# 14DoF_MPU9150_ADXL375.net
KiCad netlist of a schematic drawn in EAGLE
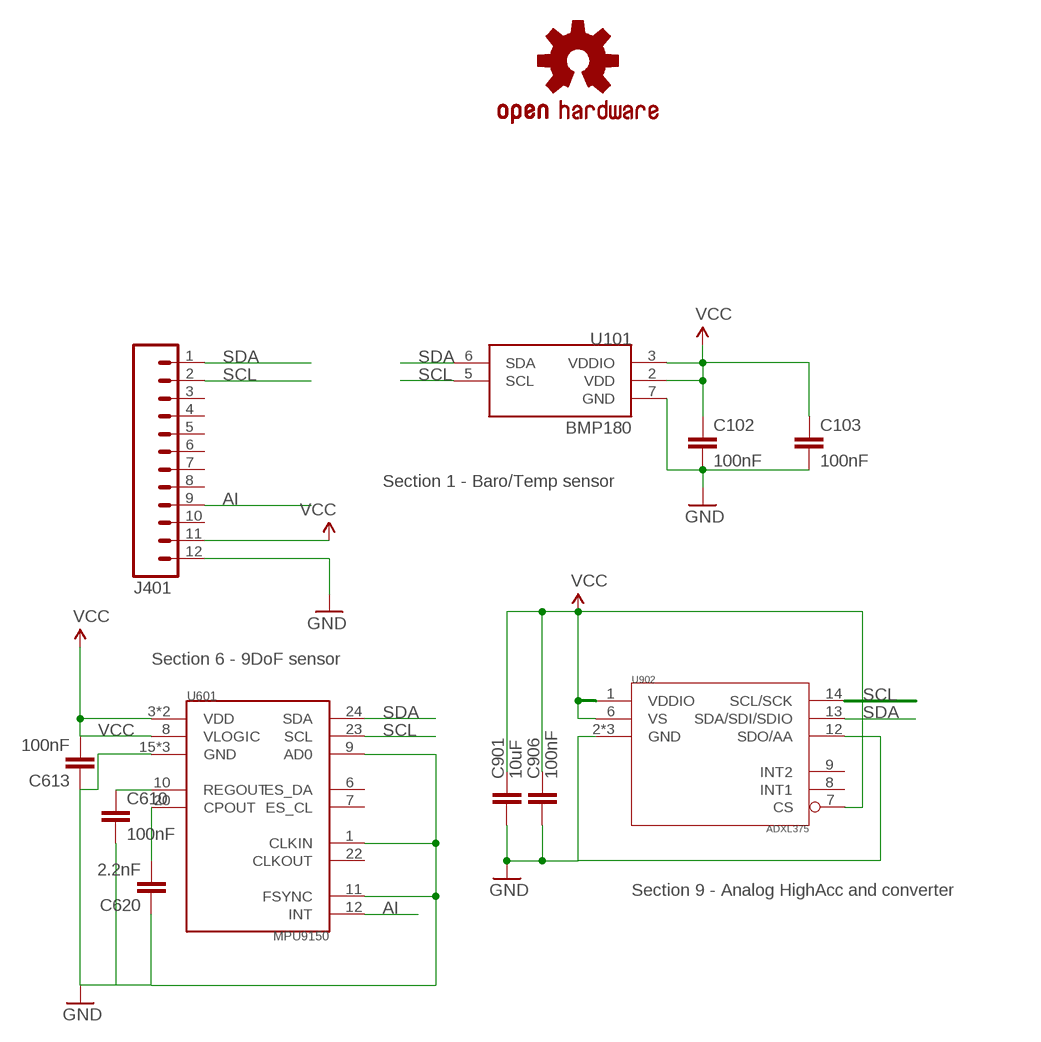
[diagram p0: schematic, sheet 1]

(export (version "E")
  (design (tool "Eeschema 10.0.6"))
  (components
    (comp (ref "C102")
      (value "100nF")
      (footprint "eagle-import:0603-CAP")
      (libsource (lib "eagle-import") (part "CAP0603-CAP"))
    )
    (comp (ref "C103")
      (value "100nF")
      (footprint "eagle-import:0603-CAP")
      (libsource (lib "eagle-import") (part "CAP0603-CAP"))
    )
    (comp (ref "C610")
      (value "100nF")
      (footprint "eagle-import:0603-CAP")
      (libsource (lib "eagle-import") (part "CAP0603-CAP"))
    )
    (comp (ref "C613")
      (value "100nF")
      (footprint "eagle-import:0603-CAP")
      (libsource (lib "eagle-import") (part "CAP0603-CAP"))
    )
    (comp (ref "C620")
      (value "2.2nF")
      (footprint "eagle-import:0603-CAP")
      (libsource (lib "eagle-import") (part "CAP0603-CAP"))
    )
    (comp (ref "C901")
      (value "10uF")
      (footprint "eagle-import:0603-CAP")
      (libsource (lib "eagle-import") (part "CAP0603-CAP"))
    )
    (comp (ref "C906")
      (value "100nF")
      (footprint "eagle-import:0603-CAP")
      (libsource (lib "eagle-import") (part "CAP0603-CAP"))
    )
    (comp (ref "J401")
      (value "M12PTH")
      (footprint "eagle-import:1X12")
      (libsource (lib "eagle-import") (part "M12PTH"))
    )
    (comp (ref "U$2")
      (value "OSHW-LOGOS")
      (footprint "eagle-import:OSHW-LOGO-S")
      (libsource (lib "eagle-import") (part "OSHW-LOGOS"))
    )
    (comp (ref "U101")
      (value "BMP180")
      (footprint "eagle-import:BMP180")
      (libsource (lib "eagle-import") (part "BMP180"))
    )
    (comp (ref "U601")
      (value "MPU9150")
      (footprint "eagle-import:LLGA24")
      (libsource (lib "eagle-import") (part "MPU9150"))
    )
    (comp (ref "U902")
      (value "ADXL375")
      (footprint "eagle-import:ADXL375")
      (libsource (lib "eagle-import") (part "ADXL375"))
    )
  )
  (nets
    (net (code "1") (name "/AI") (class "Default")
      (node (ref "J401") (pin "9") (pinfunction "9_9") (pintype "passive"))
      (node (ref "U601") (pin "12") (pinfunction "INT_12") (pintype "bidirectional"))
    )
    (net (code "2") (name "/SCL") (class "Default")
      (node (ref "J401") (pin "2") (pinfunction "2_2") (pintype "passive"))
      (node (ref "U101") (pin "5") (pinfunction "SCL_5") (pintype "input"))
      (node (ref "U601") (pin "23") (pinfunction "SCL_23") (pintype "bidirectional"))
      (node (ref "U902") (pin "14") (pinfunction "SCL/SCK_14") (pintype "input"))
    )
    (net (code "3") (name "/SDA") (class "Default")
      (node (ref "J401") (pin "1") (pinfunction "1_1") (pintype "passive"))
      (node (ref "U101") (pin "6") (pinfunction "SDA_6") (pintype "bidirectional"))
      (node (ref "U601") (pin "24") (pinfunction "SDA_24") (pintype "bidirectional"))
      (node (ref "U902") (pin "13") (pinfunction "SDA/SDI/SDIO_13") (pintype "bidirectional"))
    )
    (net (code "4") (name "GND") (class "Default")
      (node (ref "C102") (pin "2") (pinfunction "2_2") (pintype "passive"))
      (node (ref "C103") (pin "2") (pinfunction "2_2") (pintype "passive"))
      (node (ref "C610") (pin "2") (pinfunction "2_2") (pintype "passive"))
      (node (ref "C613") (pin "1") (pinfunction "1_1") (pintype "passive"))
      (node (ref "C620") (pin "1") (pinfunction "1_1") (pintype "passive"))
      (node (ref "C901") (pin "2") (pinfunction "2_2") (pintype "passive"))
      (node (ref "C906") (pin "2") (pinfunction "2_2") (pintype "passive"))
      (node (ref "J401") (pin "12") (pinfunction "12_12") (pintype "passive"))
      (node (ref "U101") (pin "7") (pinfunction "GND_7") (pintype "power_in"))
      (node (ref "U601") (pin "1") (pinfunction "CLKIN_1") (pintype "bidirectional"))
      (node (ref "U601") (pin "11") (pinfunction "FSYNC_11") (pintype "bidirectional"))
      (node (ref "U601") (pin "15") (pinfunction "GND_15") (pintype "bidirectional"))
      (node (ref "U601") (pin "17") (pinfunction "GND_17") (pintype "bidirectional"))
      (node (ref "U601") (pin "18") (pinfunction "GND_18") (pintype "bidirectional"))
      (node (ref "U601") (pin "9") (pinfunction "AD0_9") (pintype "bidirectional"))
      (node (ref "U902") (pin "12") (pinfunction "SDO/AA_12") (pintype "bidirectional"))
      (node (ref "U902") (pin "2") (pinfunction "GND_2") (pintype "power_in"))
      (node (ref "U902") (pin "4") (pinfunction "GND_4") (pintype "power_in"))
      (node (ref "U902") (pin "5") (pinfunction "GND_5") (pintype "power_in"))
    )
    (net (code "5") (name "Net-(U601-CPOUT)") (class "Default")
      (node (ref "C620") (pin "2") (pinfunction "2_2") (pintype "passive"))
      (node (ref "U601") (pin "20") (pinfunction "CPOUT_20") (pintype "bidirectional"))
    )
    (net (code "6") (name "Net-(U601-REGOUT)") (class "Default")
      (node (ref "C610") (pin "1") (pinfunction "1_1") (pintype "passive"))
      (node (ref "U601") (pin "10") (pinfunction "REGOUT_10") (pintype "bidirectional"))
    )
    (net (code "7") (name "VCC") (class "Default")
      (node (ref "C102") (pin "1") (pinfunction "1_1") (pintype "passive"))
      (node (ref "C103") (pin "1") (pinfunction "1_1") (pintype "passive"))
      (node (ref "C613") (pin "2") (pinfunction "2_2") (pintype "passive"))
      (node (ref "C901") (pin "1") (pinfunction "1_1") (pintype "passive"))
      (node (ref "C906") (pin "1") (pinfunction "1_1") (pintype "passive"))
      (node (ref "J401") (pin "11") (pinfunction "11_11") (pintype "passive"))
      (node (ref "U101") (pin "2") (pinfunction "VDD_2") (pintype "power_in"))
      (node (ref "U101") (pin "3") (pinfunction "VDDIO_3") (pintype "power_in"))
      (node (ref "U601") (pin "13") (pinfunction "VDD_13") (pintype "bidirectional"))
      (node (ref "U601") (pin "3") (pinfunction "VDD_3") (pintype "bidirectional"))
      (node (ref "U601") (pin "8") (pinfunction "VLOGIC_8") (pintype "bidirectional"))
      (node (ref "U902") (pin "1") (pinfunction "VDDIO_1") (pintype "power_in"))
      (node (ref "U902") (pin "6") (pinfunction "VS_6") (pintype "power_in"))
    )
    (net (code "8") (name "unconnected-(J401-Pad3)") (class "Default")
      (node (ref "J401") (pin "3") (pinfunction "3_3") (pintype "passive"))
    )
    (net (code "9") (name "unconnected-(J401-Pad4)") (class "Default")
      (node (ref "J401") (pin "4") (pinfunction "4_4") (pintype "passive"))
    )
    (net (code "10") (name "unconnected-(J401-Pad5)") (class "Default")
      (node (ref "J401") (pin "5") (pinfunction "5_5") (pintype "passive"))
    )
    (net (code "11") (name "unconnected-(J401-Pad6)") (class "Default")
      (node (ref "J401") (pin "6") (pinfunction "6_6") (pintype "passive"))
    )
    (net (code "12") (name "unconnected-(J401-Pad7)") (class "Default")
      (node (ref "J401") (pin "7") (pinfunction "7_7") (pintype "passive"))
    )
    (net (code "13") (name "unconnected-(J401-Pad8)") (class "Default")
      (node (ref "J401") (pin "8") (pinfunction "8_8") (pintype "passive"))
    )
    (net (code "14") (name "unconnected-(J401-Pad10)") (class "Default")
      (node (ref "J401") (pin "10") (pinfunction "10_10") (pintype "passive"))
    )
    (net (code "15") (name "unconnected-(U601-CLKOUT-Pad22)") (class "Default")
      (node (ref "U601") (pin "22") (pinfunction "CLKOUT_22") (pintype "bidirectional"))
    )
    (net (code "16") (name "unconnected-(U601-ES_CL-Pad7)") (class "Default")
      (node (ref "U601") (pin "7") (pinfunction "ES_CL_7") (pintype "bidirectional"))
    )
    (net (code "17") (name "unconnected-(U601-ES_DA-Pad6)") (class "Default")
      (node (ref "U601") (pin "6") (pinfunction "ES_DA_6") (pintype "bidirectional"))
    )
    (net (code "18") (name "unconnected-(U902-CS-Pad7)") (class "Default")
      (node (ref "U902") (pin "7") (pinfunction "CS_7") (pintype "input"))
    )
    (net (code "19") (name "unconnected-(U902-INT1-Pad8)") (class "Default")
      (node (ref "U902") (pin "8") (pinfunction "INT1_8") (pintype "output"))
    )
    (net (code "20") (name "unconnected-(U902-INT2-Pad9)") (class "Default")
      (node (ref "U902") (pin "9") (pinfunction "INT2_9") (pintype "output"))
    )
  )
)
